# team4-selo-atmega32u4-usb.net
KiCad netlist of a schematic drawn in EAGLE
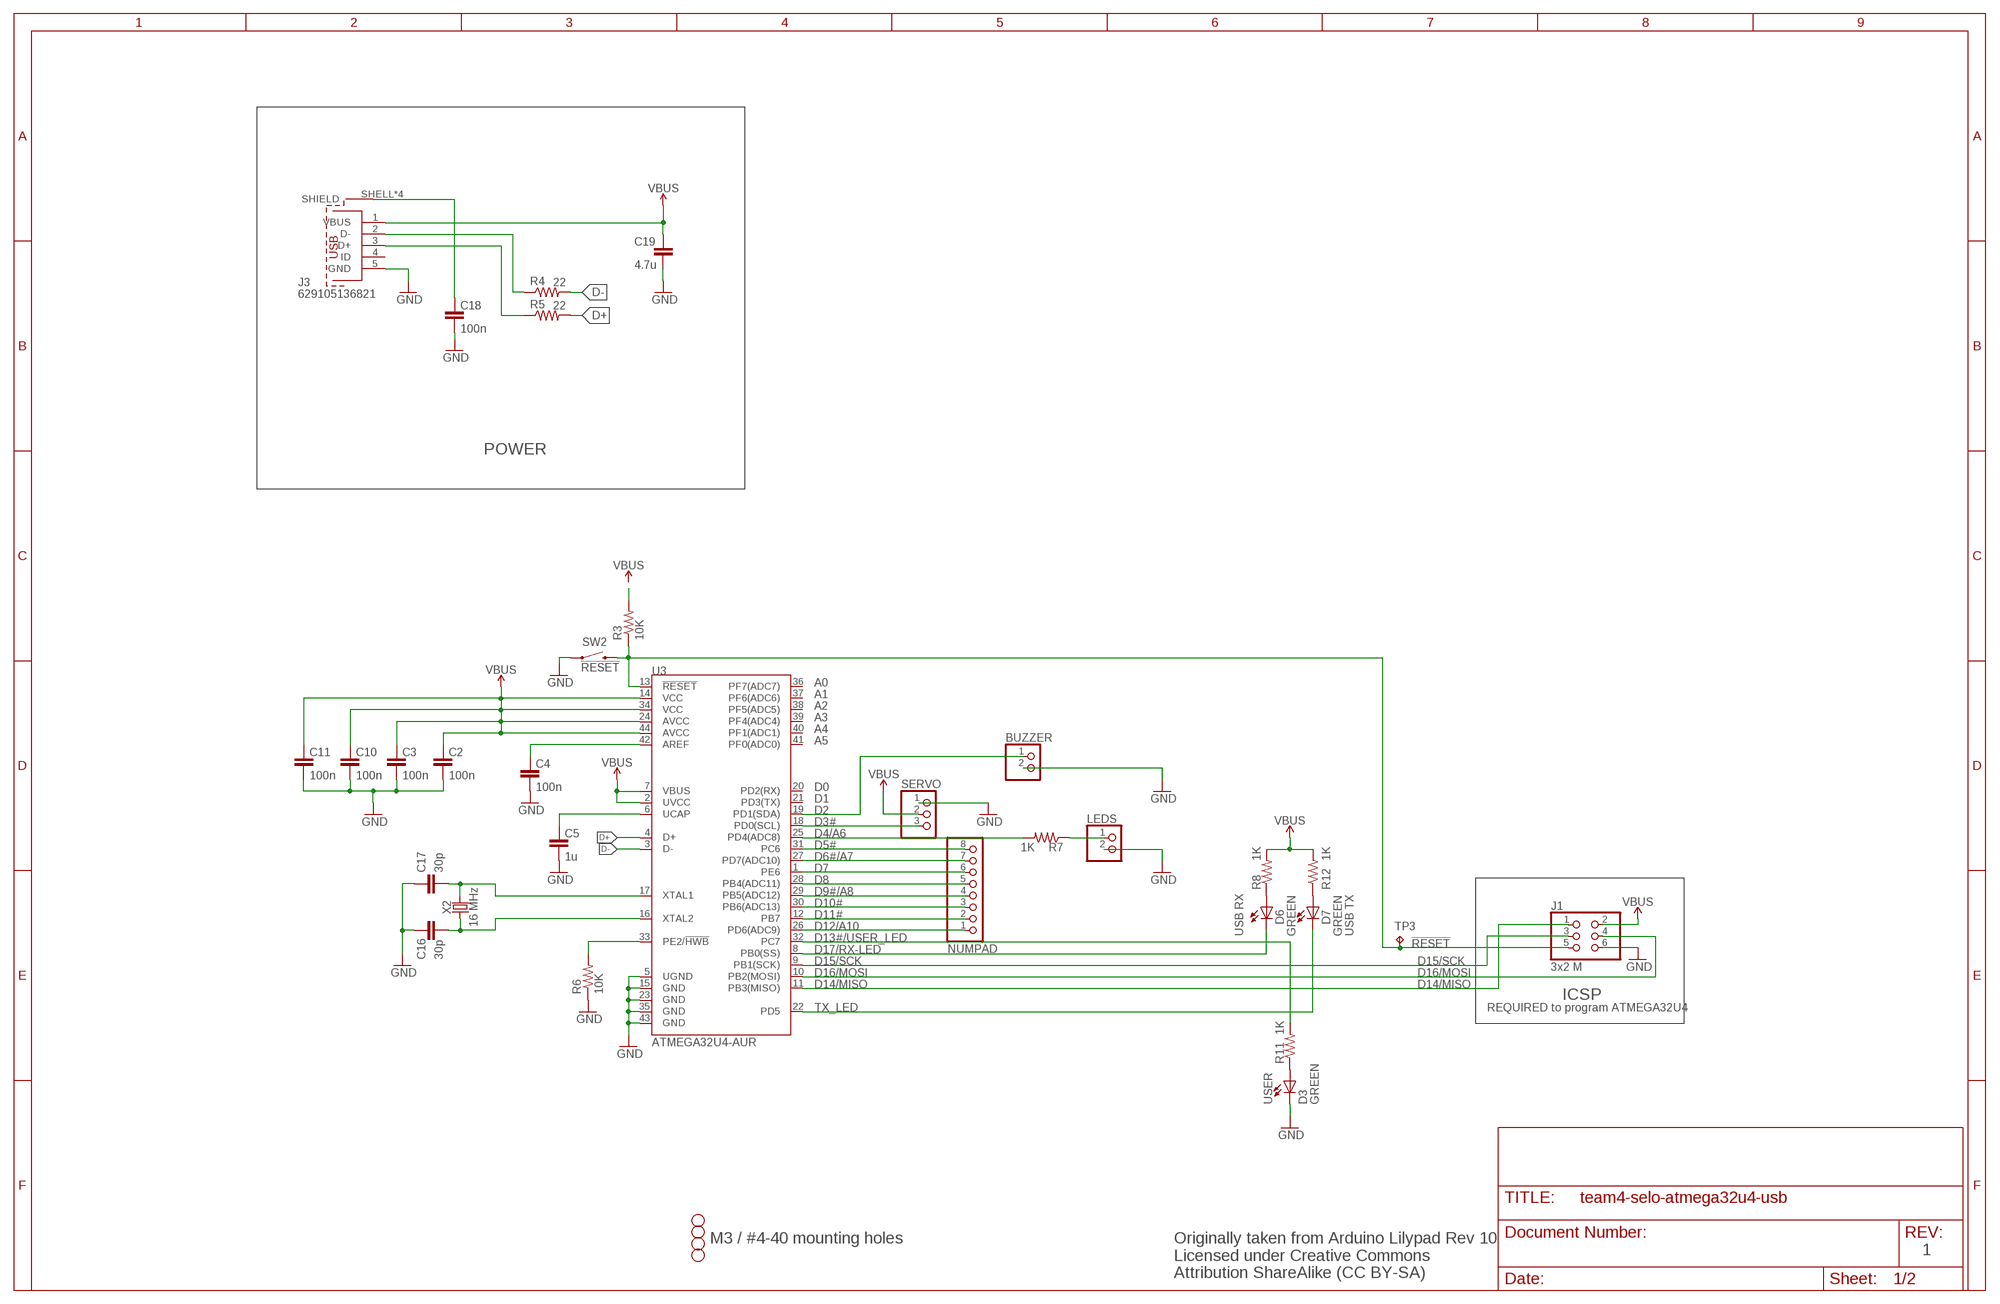
[diagram p0: schematic, sheet 1]

(export (version "E")
  (design (tool "Eeschema 10.0.6"))
  (components
    (comp (ref "BUZZER")
      (value "PINHD-1X2")
      (footprint "eagle-import:1X02")
      (libsource (lib "eagle-import") (part "PINHD-1X2"))
    )
    (comp (ref "C2")
      (value "100n")
      (footprint "eagle-import:C0805K")
      (fields (field (name "MFR") "Samsung") (field (name "MPN") "CL21B104KBCNNNC"))
      (libsource (lib "eagle-import") (part "C-EUC0805K"))
    )
    (comp (ref "C3")
      (value "100n")
      (footprint "eagle-import:C0805K")
      (fields (field (name "MFR") "Samsung") (field (name "MPN") "CL21B104KBCNNNC"))
      (libsource (lib "eagle-import") (part "C-EUC0805K"))
    )
    (comp (ref "C4")
      (value "100n")
      (footprint "eagle-import:C0805K")
      (fields (field (name "MFR") "Samsung") (field (name "MPN") "CL21B104KBCNNNC"))
      (libsource (lib "eagle-import") (part "C-EUC0805K"))
    )
    (comp (ref "C5")
      (value "1u")
      (footprint "eagle-import:C0805K")
      (fields (field (name "MFR") "Samsung") (field (name "MPN") "CL21B105KOFNNNG"))
      (libsource (lib "eagle-import") (part "C-EUC0805K"))
    )
    (comp (ref "C10")
      (value "100n")
      (footprint "eagle-import:C0805K")
      (fields (field (name "MFR") "Samsung") (field (name "MPN") "CL21B104KBCNNNC"))
      (libsource (lib "eagle-import") (part "C-EUC0805K"))
    )
    (comp (ref "C11")
      (value "100n")
      (footprint "eagle-import:C0805K")
      (fields (field (name "MFR") "Samsung") (field (name "MPN") "CL21B104KBCNNNC"))
      (libsource (lib "eagle-import") (part "C-EUC0805K"))
    )
    (comp (ref "C16")
      (value "30p")
      (footprint "eagle-import:C0805K")
      (fields (field (name "MFR") "Samsung") (field (name "MPN") "CL21C300JBANNNC"))
      (libsource (lib "eagle-import") (part "C-EUC0805K"))
    )
    (comp (ref "C17")
      (value "30p")
      (footprint "eagle-import:C0805K")
      (fields (field (name "MFR") "Samsung") (field (name "MPN") "CL21C180JBANNNC"))
      (libsource (lib "eagle-import") (part "C-EUC0805K"))
    )
    (comp (ref "C18")
      (value "100n")
      (footprint "eagle-import:C0805K")
      (fields (field (name "MFR") "Samsung") (field (name "MPN") "CL21B104KBCNNNC"))
      (libsource (lib "eagle-import") (part "C-EUC0805K"))
    )
    (comp (ref "C19")
      (value "4.7u")
      (footprint "eagle-import:C0805K")
      (fields (field (name "MFR") "Samsung") (field (name "MPN") "CL21A475KOFNNNE"))
      (libsource (lib "eagle-import") (part "C-EUC0805K"))
    )
    (comp (ref "D3")
      (value "GREEN")
      (footprint "eagle-import:CHIP-LED0805")
      (fields (field (name "MFR") "Würth Elektronik") (field (name "MPN") "150080GS75000"))
      (libsource (lib "eagle-import") (part "LEDCHIP-LED0805"))
    )
    (comp (ref "D6")
      (value "GREEN")
      (footprint "eagle-import:CHIP-LED0805")
      (fields (field (name "MFR") "Würth Elektronik") (field (name "MPN") "150080GS75000"))
      (libsource (lib "eagle-import") (part "LEDCHIP-LED0805"))
    )
    (comp (ref "D7")
      (value "GREEN")
      (footprint "eagle-import:CHIP-LED0805")
      (fields (field (name "MFR") "Würth Elektronik") (field (name "MPN") "150080GS75000"))
      (libsource (lib "eagle-import") (part "LEDCHIP-LED0805"))
    )
    (comp (ref "H1")
      (value "STAND-OFF")
      (footprint "eagle-import:STAND-OFF")
      (libsource (lib "eagle-import") (part "STAND-OFF"))
    )
    (comp (ref "H2")
      (value "STAND-OFF")
      (footprint "eagle-import:STAND-OFF")
      (libsource (lib "eagle-import") (part "STAND-OFF"))
    )
    (comp (ref "H3")
      (value "STAND-OFF")
      (footprint "eagle-import:STAND-OFF")
      (libsource (lib "eagle-import") (part "STAND-OFF"))
    )
    (comp (ref "H4")
      (value "STAND-OFF")
      (footprint "eagle-import:STAND-OFF")
      (libsource (lib "eagle-import") (part "STAND-OFF"))
    )
    (comp (ref "J1")
      (value "3x2 M")
      (footprint "eagle-import:2X03")
      (fields (field (name "MFR") "Harwin") (field (name "MPN") "M20-9980345"))
      (libsource (lib "eagle-import") (part "PINHD-2X3"))
    )
    (comp (ref "J3")
      (value "629105136821")
      (footprint "eagle-import:629105136821")
      (fields (field (name "MFR") "Wurth"))
      (libsource (lib "eagle-import") (part "629105136821"))
    )
    (comp (ref "LEDS")
      (value "PINHD-1X2")
      (footprint "eagle-import:1X02")
      (libsource (lib "eagle-import") (part "PINHD-1X2"))
    )
    (comp (ref "NUMPAD")
      (value "PINHD-1X8")
      (footprint "eagle-import:1X08")
      (libsource (lib "eagle-import") (part "PINHD-1X8"))
    )
    (comp (ref "R3")
      (value "10K")
      (footprint "eagle-import:R0805")
      (fields (field (name "MFR") "Yageo") (field (name "MPN") "RC0805FR-0710KL"))
      (libsource (lib "eagle-import") (part "R-US_R0805"))
    )
    (comp (ref "R4")
      (value "22")
      (footprint "eagle-import:R0805")
      (fields (field (name "MFR") "Yageo") (field (name "MPN") "RC0805FR-0722RL"))
      (libsource (lib "eagle-import") (part "R-US_R0805"))
    )
    (comp (ref "R5")
      (value "22")
      (footprint "eagle-import:R0805")
      (fields (field (name "MFR") "Yageo") (field (name "MPN") "RC0805FR-0722RL"))
      (libsource (lib "eagle-import") (part "R-US_R0805"))
    )
    (comp (ref "R6")
      (value "10K")
      (footprint "eagle-import:R0805")
      (fields (field (name "MFR") "Yageo") (field (name "MPN") "RC0805FR-0710KL"))
      (libsource (lib "eagle-import") (part "R-US_R0805"))
    )
    (comp (ref "R7")
      (value "1K")
      (footprint "eagle-import:R0805")
      (fields (field (name "MFR") "Yageo") (field (name "MPN") "RC0805FR-071KL"))
      (libsource (lib "eagle-import") (part "R-US_R0805"))
    )
    (comp (ref "R8")
      (value "1K")
      (footprint "eagle-import:R0805")
      (fields (field (name "MFR") "Yageo") (field (name "MPN") "RC0805FR-071KL"))
      (libsource (lib "eagle-import") (part "R-US_R0805"))
    )
    (comp (ref "R11")
      (value "1K")
      (footprint "eagle-import:R0805")
      (fields (field (name "MFR") "Yageo") (field (name "MPN") "RC0805FR-071KL"))
      (libsource (lib "eagle-import") (part "R-US_R0805"))
    )
    (comp (ref "R12")
      (value "1K")
      (footprint "eagle-import:R0805")
      (fields (field (name "MFR") "Yageo") (field (name "MPN") "RC0805FR-071KL"))
      (libsource (lib "eagle-import") (part "R-US_R0805"))
    )
    (comp (ref "SERVO")
      (value "PINHD-1X3")
      (footprint "eagle-import:1X03")
      (libsource (lib "eagle-import") (part "PINHD-1X3"))
    )
    (comp (ref "SW2")
      (value "!RESET")
      (footprint "eagle-import:TACTILE_SWITCH_SMD")
      (fields (field (name "MFR") "C&K") (field (name "MPN") "RS-187R05A2-DS MT RT"))
      (libsource (lib "eagle-import") (part "SWITCH-MOMENTARY-2SMD"))
    )
    (comp (ref "TP3")
      (value "TPPAD1-13")
      (footprint "eagle-import:P1-13")
      (libsource (lib "eagle-import") (part "TPPAD1-13"))
    )
    (comp (ref "U3")
      (value "ATMEGA32U4-AUR")
      (footprint "eagle-import:TQFP44")
      (fields (field (name "MFR") "Microchip") (field (name "PROD_ID") "IC-10828"))
      (libsource (lib "eagle-import") (part "ATMEGA32U4TQFP-44"))
    )
    (comp (ref "X2")
      (value "16 MHz")
      (footprint "eagle-import:HC49UP")
      (fields (field (name "MFR") "ECS") (field (name "MPN") "ECS-160-18-5PX-TR"))
      (libsource (lib "eagle-import") (part "CRYSTALSMD-HC49UP"))
    )
  )
  (nets
    (net (code "1") (name "D+") (class "Default")
      (node (ref "R5") (pin "2") (pinfunction "2_2") (pintype "passive"))
      (node (ref "U3") (pin "4") (pinfunction "D+_4") (pintype "bidirectional"))
    )
    (net (code "2") (name "D-") (class "Default")
      (node (ref "R4") (pin "2") (pinfunction "2_2") (pintype "passive"))
      (node (ref "U3") (pin "3") (pinfunction "D-_3") (pintype "bidirectional"))
    )
    (net (code "3") (name "D13#{slash}USER_LED") (class "Default")
      (node (ref "R11") (pin "2") (pinfunction "2_2") (pintype "passive"))
      (node (ref "U3") (pin "32") (pinfunction "PC7_32") (pintype "bidirectional"))
    )
    (net (code "4") (name "D14{slash}MISO") (class "Default")
      (node (ref "J1") (pin "1") (pinfunction "1_1") (pintype "passive"))
      (node (ref "U3") (pin "11") (pinfunction "PB3(MISO)_11") (pintype "bidirectional"))
    )
    (net (code "5") (name "D15{slash}SCK") (class "Default")
      (node (ref "J1") (pin "3") (pinfunction "3_3") (pintype "passive"))
      (node (ref "U3") (pin "9") (pinfunction "PB1(SCK)_9") (pintype "bidirectional"))
    )
    (net (code "6") (name "D16{slash}MOSI") (class "Default")
      (node (ref "J1") (pin "4") (pinfunction "4_4") (pintype "passive"))
      (node (ref "U3") (pin "10") (pinfunction "PB2(MOSI)_10") (pintype "bidirectional"))
    )
    (net (code "7") (name "D17{slash}RX-LED") (class "Default")
      (node (ref "D6") (pin "C") (pinfunction "C_C") (pintype "passive"))
      (node (ref "U3") (pin "8") (pinfunction "PB0(SS)_8") (pintype "bidirectional"))
    )
    (net (code "8") (name "GND") (class "Default")
      (node (ref "BUZZER") (pin "2") (pinfunction "2_2") (pintype "passive"))
      (node (ref "C10") (pin "2") (pinfunction "2_2") (pintype "passive"))
      (node (ref "C11") (pin "2") (pinfunction "2_2") (pintype "passive"))
      (node (ref "C16") (pin "2") (pinfunction "2_2") (pintype "passive"))
      (node (ref "C17") (pin "2") (pinfunction "2_2") (pintype "passive"))
      (node (ref "C18") (pin "2") (pinfunction "2_2") (pintype "passive"))
      (node (ref "C19") (pin "2") (pinfunction "2_2") (pintype "passive"))
      (node (ref "C2") (pin "2") (pinfunction "2_2") (pintype "passive"))
      (node (ref "C3") (pin "2") (pinfunction "2_2") (pintype "passive"))
      (node (ref "C4") (pin "2") (pinfunction "2_2") (pintype "passive"))
      (node (ref "C5") (pin "2") (pinfunction "2_2") (pintype "passive"))
      (node (ref "D3") (pin "C") (pinfunction "C_C") (pintype "passive"))
      (node (ref "J1") (pin "6") (pinfunction "6_6") (pintype "passive"))
      (node (ref "J3") (pin "5") (pinfunction "GND_5") (pintype "passive"))
      (node (ref "LEDS") (pin "2") (pinfunction "2_2") (pintype "passive"))
      (node (ref "R6") (pin "1") (pinfunction "1_1") (pintype "passive"))
      (node (ref "SERVO") (pin "1") (pinfunction "1_1") (pintype "passive"))
      (node (ref "SW2") (pin "1") (pinfunction "1_1") (pintype "passive"))
      (node (ref "U3") (pin "15") (pinfunction "GND_15") (pintype "bidirectional"))
      (node (ref "U3") (pin "23") (pinfunction "GND_23") (pintype "bidirectional"))
      (node (ref "U3") (pin "35") (pinfunction "GND_35") (pintype "bidirectional"))
      (node (ref "U3") (pin "43") (pinfunction "GND_43") (pintype "bidirectional"))
      (node (ref "U3") (pin "5") (pinfunction "UGND_5") (pintype "bidirectional"))
    )
    (net (code "9") (name "Net-(C18-Pad1)") (class "Default")
      (node (ref "C18") (pin "1") (pinfunction "1_1") (pintype "passive"))
      (node (ref "J3") (pin "SHELL") (pinfunction "SHIELD_SHELL") (pintype "passive"))
      (node (ref "J3") (pin "SHELL1") (pinfunction "SHIELD_SHELL1") (pintype "passive"))
      (node (ref "J3") (pin "SHELL2") (pinfunction "SHIELD_SHELL2") (pintype "passive"))
      (node (ref "J3") (pin "SHELL3") (pinfunction "SHIELD_SHELL3") (pintype "passive"))
    )
    (net (code "10") (name "Net-(D3-PadA)") (class "Default")
      (node (ref "D3") (pin "A") (pinfunction "A_A") (pintype "passive"))
      (node (ref "R11") (pin "1") (pinfunction "1_1") (pintype "passive"))
    )
    (net (code "11") (name "Net-(D6-PadA)") (class "Default")
      (node (ref "D6") (pin "A") (pinfunction "A_A") (pintype "passive"))
      (node (ref "R8") (pin "1") (pinfunction "1_1") (pintype "passive"))
    )
    (net (code "12") (name "Net-(D7-PadA)") (class "Default")
      (node (ref "D7") (pin "A") (pinfunction "A_A") (pintype "passive"))
      (node (ref "R12") (pin "1") (pinfunction "1_1") (pintype "passive"))
    )
    (net (code "13") (name "Net-(J3-D+)") (class "Default")
      (node (ref "J3") (pin "3") (pinfunction "D+_3") (pintype "passive"))
      (node (ref "R5") (pin "1") (pinfunction "1_1") (pintype "passive"))
    )
    (net (code "14") (name "Net-(J3-D-)") (class "Default")
      (node (ref "J3") (pin "2") (pinfunction "D-_2") (pintype "passive"))
      (node (ref "R4") (pin "1") (pinfunction "1_1") (pintype "passive"))
    )
    (net (code "15") (name "Net-(LEDS-Pad1)") (class "Default")
      (node (ref "LEDS") (pin "1") (pinfunction "1_1") (pintype "passive"))
      (node (ref "R7") (pin "1") (pinfunction "1_1") (pintype "passive"))
    )
    (net (code "16") (name "Net-(U3-AREF)") (class "Default")
      (node (ref "C4") (pin "1") (pinfunction "1_1") (pintype "passive"))
      (node (ref "U3") (pin "42") (pinfunction "AREF_42") (pintype "bidirectional"))
    )
    (net (code "17") (name "Net-(U3-PB4(ADC11))") (class "Default")
      (node (ref "NUMPAD") (pin "5") (pinfunction "5_5") (pintype "passive"))
      (node (ref "U3") (pin "28") (pinfunction "PB4(ADC11)_28") (pintype "bidirectional"))
    )
    (net (code "18") (name "Net-(U3-PB5(ADC12))") (class "Default")
      (node (ref "NUMPAD") (pin "4") (pinfunction "4_4") (pintype "passive"))
      (node (ref "U3") (pin "29") (pinfunction "PB5(ADC12)_29") (pintype "bidirectional"))
    )
    (net (code "19") (name "Net-(U3-PB6(ADC13))") (class "Default")
      (node (ref "NUMPAD") (pin "3") (pinfunction "3_3") (pintype "passive"))
      (node (ref "U3") (pin "30") (pinfunction "PB6(ADC13)_30") (pintype "bidirectional"))
    )
    (net (code "20") (name "Net-(U3-PB7)") (class "Default")
      (node (ref "NUMPAD") (pin "2") (pinfunction "2_2") (pintype "passive"))
      (node (ref "U3") (pin "12") (pinfunction "PB7_12") (pintype "bidirectional"))
    )
    (net (code "21") (name "Net-(U3-PC6)") (class "Default")
      (node (ref "NUMPAD") (pin "8") (pinfunction "8_8") (pintype "passive"))
      (node (ref "U3") (pin "31") (pinfunction "PC6_31") (pintype "bidirectional"))
    )
    (net (code "22") (name "Net-(U3-PD0(SCL))") (class "Default")
      (node (ref "SERVO") (pin "3") (pinfunction "3_3") (pintype "passive"))
      (node (ref "U3") (pin "18") (pinfunction "PD0(SCL)_18") (pintype "bidirectional"))
    )
    (net (code "23") (name "Net-(U3-PD1(SDA))") (class "Default")
      (node (ref "BUZZER") (pin "1") (pinfunction "1_1") (pintype "passive"))
      (node (ref "U3") (pin "19") (pinfunction "PD1(SDA)_19") (pintype "bidirectional"))
    )
    (net (code "24") (name "Net-(U3-PD4(ADC8))") (class "Default")
      (node (ref "R7") (pin "2") (pinfunction "2_2") (pintype "passive"))
      (node (ref "U3") (pin "25") (pinfunction "PD4(ADC8)_25") (pintype "bidirectional"))
    )
    (net (code "25") (name "Net-(U3-PD6(ADC9))") (class "Default")
      (node (ref "NUMPAD") (pin "1") (pinfunction "1_1") (pintype "passive"))
      (node (ref "U3") (pin "26") (pinfunction "PD6(ADC9)_26") (pintype "bidirectional"))
    )
    (net (code "26") (name "Net-(U3-PD7(ADC10))") (class "Default")
      (node (ref "NUMPAD") (pin "7") (pinfunction "7_7") (pintype "passive"))
      (node (ref "U3") (pin "27") (pinfunction "PD7(ADC10)_27") (pintype "bidirectional"))
    )
    (net (code "27") (name "Net-(U3-PE2{slash}~{HWB})") (class "Default")
      (node (ref "R6") (pin "2") (pinfunction "2_2") (pintype "passive"))
      (node (ref "U3") (pin "33") (pinfunction "PE2/~{HWB}_33") (pintype "bidirectional"))
    )
    (net (code "28") (name "Net-(U3-PE6)") (class "Default")
      (node (ref "NUMPAD") (pin "6") (pinfunction "6_6") (pintype "passive"))
      (node (ref "U3") (pin "1") (pinfunction "PE6_1") (pintype "bidirectional"))
    )
    (net (code "29") (name "Net-(U3-UCAP)") (class "Default")
      (node (ref "C5") (pin "1") (pinfunction "1_1") (pintype "passive"))
      (node (ref "U3") (pin "6") (pinfunction "UCAP_6") (pintype "bidirectional"))
    )
    (net (code "30") (name "Net-(U3-XTAL1)") (class "Default")
      (node (ref "C17") (pin "1") (pinfunction "1_1") (pintype "passive"))
      (node (ref "U3") (pin "17") (pinfunction "XTAL1_17") (pintype "bidirectional"))
      (node (ref "X2") (pin "2") (pinfunction "2_2") (pintype "passive"))
    )
    (net (code "31") (name "Net-(U3-XTAL2)") (class "Default")
      (node (ref "C16") (pin "1") (pinfunction "1_1") (pintype "passive"))
      (node (ref "U3") (pin "16") (pinfunction "XTAL2_16") (pintype "bidirectional"))
      (node (ref "X2") (pin "1") (pinfunction "1_1") (pintype "passive"))
    )
    (net (code "32") (name "TX_LED") (class "Default")
      (node (ref "D7") (pin "C") (pinfunction "C_C") (pintype "passive"))
      (node (ref "U3") (pin "22") (pinfunction "PD5_22") (pintype "bidirectional"))
    )
    (net (code "33") (name "VBUS") (class "Default")
      (node (ref "C10") (pin "1") (pinfunction "1_1") (pintype "passive"))
      (node (ref "C11") (pin "1") (pinfunction "1_1") (pintype "passive"))
      (node (ref "C19") (pin "1") (pinfunction "1_1") (pintype "passive"))
      (node (ref "C2") (pin "1") (pinfunction "1_1") (pintype "passive"))
      (node (ref "C3") (pin "1") (pinfunction "1_1") (pintype "passive"))
      (node (ref "J1") (pin "2") (pinfunction "2_2") (pintype "passive"))
      (node (ref "J3") (pin "1") (pinfunction "VBUS_1") (pintype "passive"))
      (node (ref "R12") (pin "2") (pinfunction "2_2") (pintype "passive"))
      (node (ref "R8") (pin "2") (pinfunction "2_2") (pintype "passive"))
      (node (ref "SERVO") (pin "2") (pinfunction "2_2") (pintype "passive"))
      (node (ref "U3") (pin "14") (pinfunction "VCC_14") (pintype "bidirectional"))
      (node (ref "U3") (pin "2") (pinfunction "UVCC_2") (pintype "bidirectional"))
      (node (ref "U3") (pin "24") (pinfunction "AVCC_24") (pintype "bidirectional"))
      (node (ref "U3") (pin "34") (pinfunction "VCC_34") (pintype "bidirectional"))
      (node (ref "U3") (pin "44") (pinfunction "AVCC_44") (pintype "bidirectional"))
      (node (ref "U3") (pin "7") (pinfunction "VBUS_7") (pintype "bidirectional"))
    )
    (net (code "34") (name "unconnected-(J3-ID-Pad4)") (class "Default")
      (node (ref "J3") (pin "4") (pinfunction "ID_4") (pintype "passive"))
    )
    (net (code "35") (name "unconnected-(R3-Pad2)") (class "Default")
      (node (ref "R3") (pin "2") (pinfunction "2_2") (pintype "passive"))
    )
    (net (code "36") (name "unconnected-(U3-PD2(RX)-Pad20)") (class "Default")
      (node (ref "U3") (pin "20") (pinfunction "PD2(RX)_20") (pintype "bidirectional"))
    )
    (net (code "37") (name "unconnected-(U3-PD3(TX)-Pad21)") (class "Default")
      (node (ref "U3") (pin "21") (pinfunction "PD3(TX)_21") (pintype "bidirectional"))
    )
    (net (code "38") (name "unconnected-(U3-PF0(ADC0)-Pad41)") (class "Default")
      (node (ref "U3") (pin "41") (pinfunction "PF0(ADC0)_41") (pintype "bidirectional"))
    )
    (net (code "39") (name "unconnected-(U3-PF1(ADC1)-Pad40)") (class "Default")
      (node (ref "U3") (pin "40") (pinfunction "PF1(ADC1)_40") (pintype "bidirectional"))
    )
    (net (code "40") (name "unconnected-(U3-PF4(ADC4)-Pad39)") (class "Default")
      (node (ref "U3") (pin "39") (pinfunction "PF4(ADC4)_39") (pintype "bidirectional"))
    )
    (net (code "41") (name "unconnected-(U3-PF5(ADC5)-Pad38)") (class "Default")
      (node (ref "U3") (pin "38") (pinfunction "PF5(ADC5)_38") (pintype "bidirectional"))
    )
    (net (code "42") (name "unconnected-(U3-PF6(ADC6)-Pad37)") (class "Default")
      (node (ref "U3") (pin "37") (pinfunction "PF6(ADC6)_37") (pintype "bidirectional"))
    )
    (net (code "43") (name "unconnected-(U3-PF7(ADC7)-Pad36)") (class "Default")
      (node (ref "U3") (pin "36") (pinfunction "PF7(ADC7)_36") (pintype "bidirectional"))
    )
    (net (code "44") (name "~{RESET}") (class "Default")
      (node (ref "J1") (pin "5") (pinfunction "5_5") (pintype "passive"))
      (node (ref "R3") (pin "1") (pinfunction "1_1") (pintype "passive"))
      (node (ref "SW2") (pin "3") (pinfunction "2_3") (pintype "passive"))
      (node (ref "TP3") (pin "TP") (pinfunction "TP_TP") (pintype "input"))
      (node (ref "U3") (pin "13") (pinfunction "~{RESET}_13") (pintype "bidirectional"))
    )
  )
)
